# design.net
KiCad netlist of a schematic drawn in Altium Designer
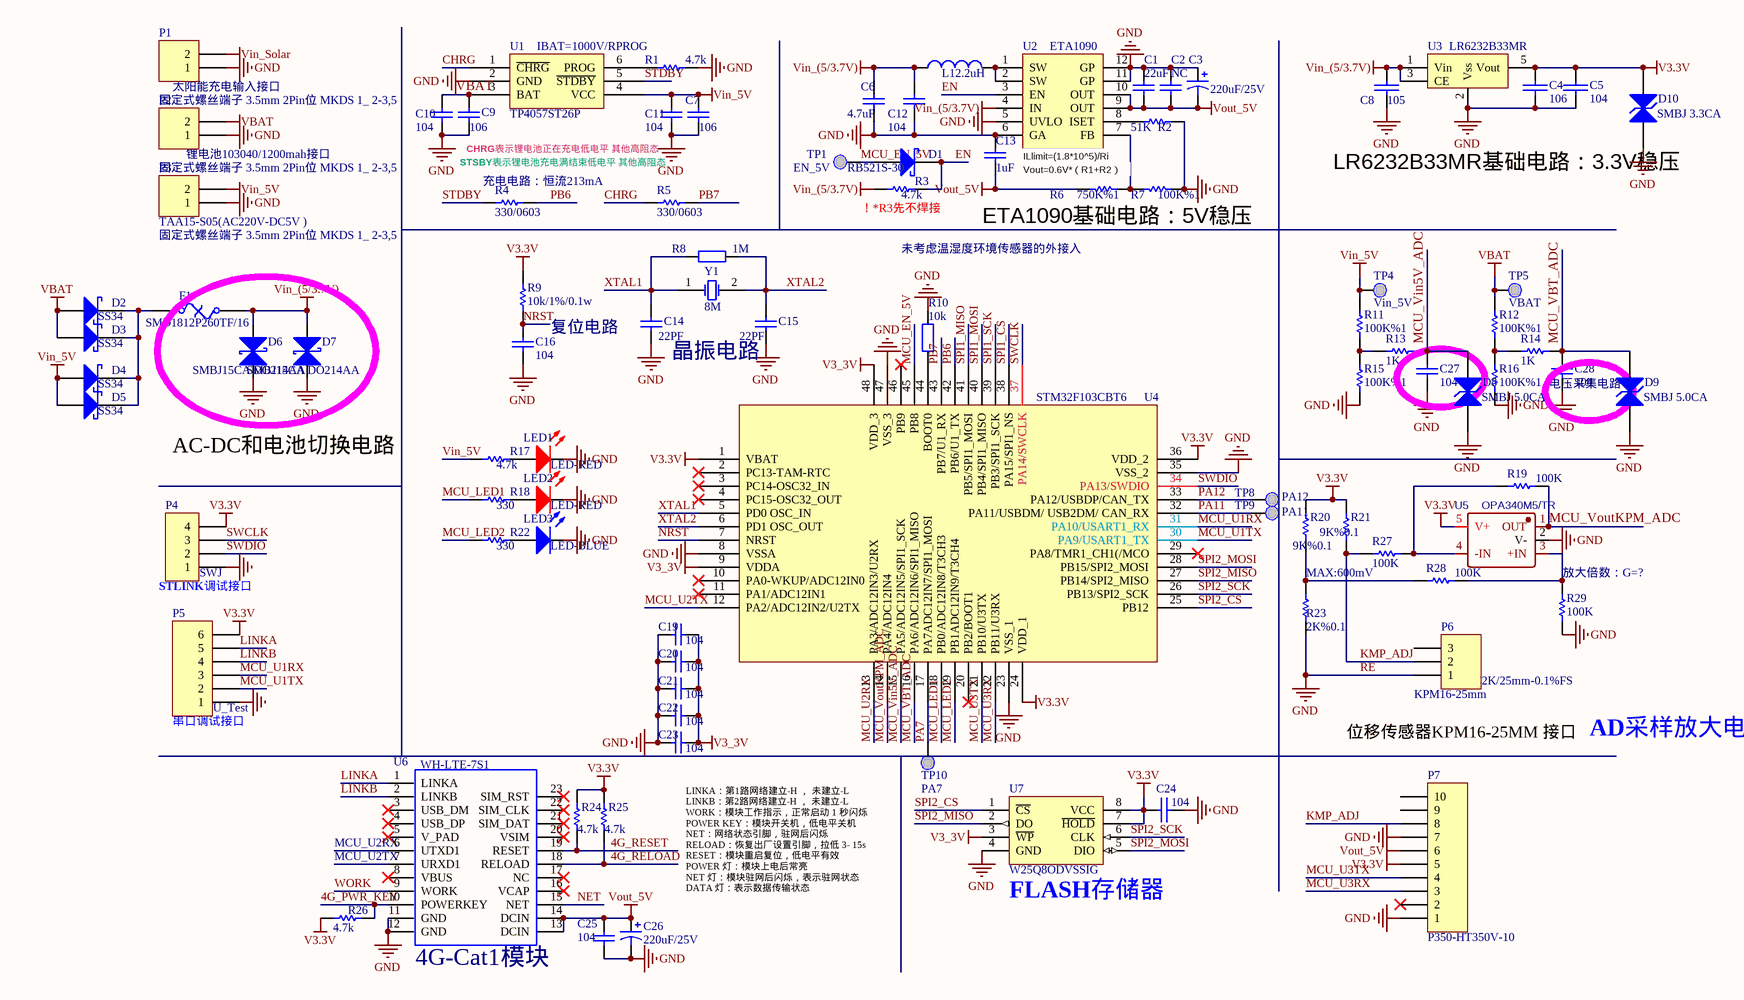
[diagram p0: 位移（应变）监测站.SchDoc]

(export (version "E")
  (design (tool "Eeschema 10.0.6"))
  (components
    (comp (ref "C1")
      (value "22uF")
      (footprint "C0805")
      (description "Capacitor")
      (fields (field (name "PUBLISHER") "Altium Limited"))
      (libsource (lib "Miscellaneous Devices") (part "Cap"))
    )
    (comp (ref "C2")
      (value "NC")
      (footprint "C0805")
      (description "Capacitor")
      (fields (field (name "Comment") "Cap") (field (name "PUBLISHER") "Altium Limited"))
      (libsource (lib "Miscellaneous Devices") (part "Cap"))
    )
    (comp (ref "C3")
      (value "220uF/25V")
      (footprint "C_6032")
      (description "Polarized Capacitor (Radial)")
      (fields (field (name "PUBLISHER") "Altium Limited"))
      (libsource (lib "Miscellaneous Devices") (part "Cap Pol1"))
    )
    (comp (ref "C4")
      (value "106")
      (footprint "C0603")
      (description "贴片电容")
      (libsource (lib "My_library") (part "CAP_1"))
    )
    (comp (ref "C5")
      (value "104")
      (footprint "C0603")
      (description "贴片电容")
      (libsource (lib "My_library") (part "CAP_1"))
    )
    (comp (ref "C6")
      (value "4.7uF")
      (footprint "C0603")
      (description "Capacitor")
      (fields (field (name "Comment") "Cap") (field (name "PUBLISHER") "Altium Limited"))
      (libsource (lib "Miscellaneous Devices") (part "Cap"))
    )
    (comp (ref "C7")
      (value "106")
      (footprint "C0603")
      (description "贴片电容")
      (fields (field (name "PUBLISHER") "Altium Limited"))
      (libsource (lib "*") (part "CAP"))
    )
    (comp (ref "C8")
      (value "105")
      (footprint "C0603")
      (description "贴片电容")
      (libsource (lib "My_library") (part "CAP_1"))
    )
    (comp (ref "C9")
      (value "106")
      (footprint "C0603")
      (description "贴片电容")
      (fields (field (name "PUBLISHER") "Altium Limited"))
      (libsource (lib "*") (part "CAP"))
    )
    (comp (ref "C10")
      (value "104")
      (footprint "C0603")
      (description "贴片电容")
      (fields (field (name "PUBLISHER") "Altium Limited"))
      (libsource (lib "*") (part "CAP"))
    )
    (comp (ref "C11")
      (value "104")
      (footprint "C0603")
      (description "贴片电容")
      (fields (field (name "PUBLISHER") "Altium Limited"))
      (libsource (lib "*") (part "CAP"))
    )
    (comp (ref "C12")
      (value "104")
      (footprint "C0603")
      (description "Capacitor")
      (fields (field (name "Comment") "Cap") (field (name "PUBLISHER") "Altium Limited"))
      (libsource (lib "Miscellaneous Devices") (part "Cap"))
    )
    (comp (ref "C13")
      (value "1uF")
      (footprint "C0603")
      (description "Capacitor")
      (fields (field (name "PUBLISHER") "Altium Limited"))
      (libsource (lib "Miscellaneous Devices") (part "Cap"))
    )
    (comp (ref "C14")
      (value "22PF")
      (footprint "C0603")
      (description "Capacitor")
      (fields (field (name "PUBLISHER") "Altium Limited"))
      (libsource (lib "Miscellaneous Devices") (part "Cap"))
    )
    (comp (ref "C15")
      (value "22PF")
      (footprint "C0603")
      (description "Capacitor")
      (fields (field (name "PUBLISHER") "Altium Limited"))
      (libsource (lib "Miscellaneous Devices") (part "Cap"))
    )
    (comp (ref "C16")
      (value "104")
      (footprint "C0603")
      (description "Capacitor")
      (fields (field (name "PUBLISHER") "Altium Limited"))
      (libsource (lib "*") (part "Cap"))
    )
    (comp (ref "C19")
      (value "104")
      (footprint "C0603")
      (description "Capacitor")
      (fields (field (name "PUBLISHER") "Altium Limited"))
      (libsource (lib "*") (part "CAP"))
    )
    (comp (ref "C20")
      (value "104")
      (footprint "C0603")
      (description "Capacitor")
      (fields (field (name "PUBLISHER") "Altium Limited"))
      (libsource (lib "*") (part "CAP"))
    )
    (comp (ref "C21")
      (value "104")
      (footprint "C0603")
      (description "Capacitor")
      (fields (field (name "PUBLISHER") "Altium Limited"))
      (libsource (lib "*") (part "CAP"))
    )
    (comp (ref "C22")
      (value "104")
      (footprint "C0603")
      (description "Capacitor")
      (fields (field (name "PUBLISHER") "Altium Limited"))
      (libsource (lib "*") (part "CAP"))
    )
    (comp (ref "C23")
      (value "104")
      (footprint "C0603")
      (description "Capacitor")
      (fields (field (name "PUBLISHER") "Altium Limited"))
      (libsource (lib "*") (part "CAP"))
    )
    (comp (ref "C24")
      (value "104")
      (footprint "C0603")
      (description "贴片电容")
      (libsource (lib "My_library") (part "CAP_1"))
    )
    (comp (ref "C25")
      (value "104")
      (footprint "C0603")
      (description "Capacitor")
      (fields (field (name "PUBLISHER") "Altium Limited"))
      (libsource (lib "*") (part "CAP"))
    )
    (comp (ref "C26")
      (value "220uF/25V")
      (footprint "C_6032")
      (description "Polarized Capacitor (Radial)")
      (fields (field (name "PUBLISHER") "Altium Limited"))
      (libsource (lib "Miscellaneous Devices") (part "Cap Pol1"))
    )
    (comp (ref "C27")
      (value "104")
      (footprint "C0603")
      (description "Capacitor")
      (fields (field (name "PUBLISHER") "Altium Limited"))
      (libsource (lib "*") (part "Cap"))
    )
    (comp (ref "C28")
      (value "104")
      (footprint "C0603")
      (description "Capacitor")
      (fields (field (name "PUBLISHER") "Altium Limited"))
      (libsource (lib "*") (part "Cap"))
    )
    (comp (ref "D1")
      (value "RB521S-30")
      (footprint "DO-214AB(SMC)")
      (description "肖特基二极管")
      (libsource (lib "My_library") (part "D Schottky"))
    )
    (comp (ref "D2")
      (value "SS34")
      (footprint "DO-214AB(SMC)")
      (description "肖特基二极管")
      (libsource (lib "My_library") (part "D Schottky"))
    )
    (comp (ref "D3")
      (value "SS34")
      (footprint "DO-214AB(SMC)")
      (description "肖特基二极管")
      (libsource (lib "My_library") (part "D Schottky"))
    )
    (comp (ref "D4")
      (value "SS34")
      (footprint "DO-214AB(SMC)")
      (description "肖特基二极管")
      (libsource (lib "My_library") (part "D Schottky"))
    )
    (comp (ref "D5")
      (value "SS34")
      (footprint "DO-214AB(SMC)")
      (description "肖特基二极管")
      (libsource (lib "My_library") (part "D Schottky"))
    )
    (comp (ref "D6")
      (value "SMBJ15CA DO214AA")
      (footprint "DO-214AA")
      (libsource (lib "自己的元器件库") (part "TVS"))
    )
    (comp (ref "D7")
      (value "SMBJ15CA DO214AA")
      (footprint "DO-214AA")
      (libsource (lib "自己的元器件库") (part "TVS"))
    )
    (comp (ref "D8")
      (value "SMBJ 5.0CA")
      (footprint "DO-214AA")
      (description "TVS")
      (libsource (lib "Miscellaneous Devices LC") (part "SMB/DO-214AA P6SMB6.8CA"))
    )
    (comp (ref "D9")
      (value "SMBJ 5.0CA")
      (footprint "DO-214AA")
      (description "TVS")
      (libsource (lib "Miscellaneous Devices LC") (part "SMB/DO-214AA P6SMB6.8CA"))
    )
    (comp (ref "D10")
      (value "SMBJ 3.3CA")
      (footprint "DO-214AA")
      (description "TVS")
      (libsource (lib "Miscellaneous Devices LC") (part "SMB/DO-214AA P6SMB6.8CA"))
    )
    (comp (ref "F1")
      (value "SMD1812P260TF/16")
      (footprint "1812")
      (description "Thermal Fuse")
      (fields (field (name "PUBLISHER") "Altium Limited"))
      (libsource (lib "Miscellaneous Devices") (part "Fuse Thermal"))
    )
    (comp (ref "L1")
      (value "2.2uH")
      (footprint "L_8X8")
      (description "Inductor")
      (fields (field (name "PUBLISHER") "Altium Limited"))
      (libsource (lib "Miscellaneous Devices") (part "Inductor"))
    )
    (comp (ref "LED1")
      (value "LED-RED")
      (footprint "0603_LED")
      (description "发光二极管")
      (libsource (lib "My_library") (part "LED-RED"))
    )
    (comp (ref "LED2")
      (value "LED-RED")
      (footprint "0603_LED")
      (description "发光二极管")
      (libsource (lib "My_library") (part "LED-RED"))
    )
    (comp (ref "LED3")
      (value "LED-BLUE")
      (footprint "0603_LED")
      (description "发光二极管")
      (libsource (lib "My_library") (part "LED-BLUE"))
    )
    (comp (ref "P1")
      (value "固定式螺丝端子 3.5mm 2Pin位 MKDS 1_ 2-3,5")
      (footprint "CONN-TH_MKDS1/2-3.5")
      (description "Header, 2-Pin")
      (fields (field (name "PUBLISHER") "Altium Limited"))
      (libsource (lib "Miscellaneous Connectors") (part "Header 2"))
    )
    (comp (ref "P2")
      (value "固定式螺丝端子 3.5mm 2Pin位 MKDS 1_ 2-3,5")
      (footprint "CONN-TH_MKDS1/2-3.5")
      (description "Header, 2-Pin")
      (fields (field (name "PUBLISHER") "Altium Limited"))
      (libsource (lib "Miscellaneous Connectors") (part "Header 2"))
    )
    (comp (ref "P3")
      (value "固定式螺丝端子 3.5mm 2Pin位 MKDS 1_ 2-3,5")
      (footprint "CONN-TH_MKDS1/2-3.5")
      (description "Header, 2-Pin")
      (fields (field (name "PUBLISHER") "Altium Limited"))
      (libsource (lib "Miscellaneous Connectors") (part "Header 2"))
    )
    (comp (ref "P4")
      (value "SWJ")
      (footprint "HDR1X4")
      (description "2.54接口，4pin")
      (libsource (lib "My_library") (part "header4"))
    )
    (comp (ref "P5")
      (value "U_Test")
      (footprint "HDR1X6")
      (description "Header, 6-Pin")
      (fields (field (name "PUBLISHER") "Altium Limited"))
      (libsource (lib "Miscellaneous Connectors") (part "Header 6"))
    )
    (comp (ref "P6")
      (value "~")
      (footprint "MHDR1X3")
      (description "航空插排（座）, 3-Pin")
      (fields (field (name "PUBLISHER") "Altium Limited"))
      (libsource (lib "Miscellaneous Connectors") (part "MHDR1X3"))
    )
    (comp (ref "P7")
      (value "P350-HT350V-10")
      (footprint "P350-HT350V-10")
      (description "Header, 10-Pin")
      (fields (field (name "PUBLISHER") "Altium Limited"))
      (libsource (lib "Miscellaneous Connectors") (part "Header 10"))
    )
    (comp (ref "R1")
      (value "4.7k")
      (footprint "R0603")
      (description "贴片电阻")
      (libsource (lib "My_library") (part "RES1"))
    )
    (comp (ref "R2")
      (value "51K")
      (footprint "R0603")
      (description "Resistor")
      (fields (field (name "PUBLISHER") "Altium Limited"))
      (libsource (lib "Miscellaneous Devices") (part "Res1"))
    )
    (comp (ref "R3")
      (value "4.7k")
      (footprint "R0603")
      (description "贴片电阻")
      (libsource (lib "My_library") (part "RES1"))
    )
    (comp (ref "R4")
      (value "330/0603")
      (footprint "R0603")
      (description "Resistor")
      (fields (field (name "PUBLISHER") "Altium Limited"))
      (libsource (lib "*") (part "Res1"))
    )
    (comp (ref "R5")
      (value "330/0603")
      (footprint "R0603")
      (description "Resistor")
      (fields (field (name "PUBLISHER") "Altium Limited"))
      (libsource (lib "*") (part "Res1"))
    )
    (comp (ref "R6")
      (value "750K%1")
      (footprint "R0603")
      (description "Resistor")
      (fields (field (name "PUBLISHER") "Altium Limited"))
      (libsource (lib "Miscellaneous Devices") (part "Res1"))
    )
    (comp (ref "R7")
      (value "100K%1")
      (footprint "R0603")
      (description "Resistor")
      (fields (field (name "PUBLISHER") "Altium Limited"))
      (libsource (lib "Miscellaneous Devices") (part "Res1"))
    )
    (comp (ref "R8")
      (value "1M")
      (footprint "R0603")
      (description "Resistor")
      (fields (field (name "PUBLISHER") "Altium Limited"))
      (libsource (lib "Miscellaneous Devices") (part "Res2"))
    )
    (comp (ref "R9")
      (value "10k/1%/0.1w")
      (footprint "R0603")
      (description "Resistor")
      (fields (field (name "PUBLISHER") "Altium Limited"))
      (libsource (lib "*") (part "res1"))
    )
    (comp (ref "R10")
      (value "10k")
      (footprint "R0603")
      (description "Resistor")
      (fields (field (name "PUBLISHER") "Altium Limited"))
      (libsource (lib "") (part "Res2_1"))
    )
    (comp (ref "R11")
      (value "100K%1")
      (footprint "R0603")
      (description "贴片电阻")
      (libsource (lib "My_library") (part "RES1"))
    )
    (comp (ref "R12")
      (value "100K%1")
      (footprint "R0603")
      (description "贴片电阻")
      (libsource (lib "My_library") (part "RES1"))
    )
    (comp (ref "R13")
      (value "1K")
      (footprint "R0603")
      (description "贴片电阻")
      (libsource (lib "My_library") (part "RES1"))
    )
    (comp (ref "R14")
      (value "1K")
      (footprint "R0603")
      (description "贴片电阻")
      (libsource (lib "My_library") (part "RES1"))
    )
    (comp (ref "R15")
      (value "100K%1")
      (footprint "R0603")
      (description "贴片电阻")
      (libsource (lib "My_library") (part "RES1"))
    )
    (comp (ref "R16")
      (value "100K%1")
      (footprint "R0603")
      (description "贴片电阻")
      (libsource (lib "My_library") (part "RES1"))
    )
    (comp (ref "R17")
      (value "4.7k")
      (footprint "R0603")
      (description "贴片电阻")
      (libsource (lib "My_library") (part "RES1"))
    )
    (comp (ref "R18")
      (value "330")
      (footprint "R0603")
      (description "贴片电阻")
      (libsource (lib "My_library") (part "RES1"))
    )
    (comp (ref "R19")
      (value "100K")
      (footprint "R0603")
      (description "贴片电阻")
      (libsource (lib "My_library") (part "RES1"))
    )
    (comp (ref "R20")
      (value "9K%0.1")
      (footprint "R0603")
      (description "贴片电阻")
      (libsource (lib "My_library") (part "RES1"))
    )
    (comp (ref "R21")
      (value "9K%0.1")
      (footprint "R0603")
      (description "贴片电阻")
      (libsource (lib "My_library") (part "RES1"))
    )
    (comp (ref "R22")
      (value "330")
      (footprint "R0603")
      (description "贴片电阻")
      (libsource (lib "My_library") (part "RES1"))
    )
    (comp (ref "R23")
      (value "2K%0.1")
      (footprint "R0603")
      (description "贴片电阻")
      (libsource (lib "My_library") (part "RES1"))
    )
    (comp (ref "R24")
      (value "4.7k")
      (footprint "R0603")
      (description "Resistor")
      (fields (field (name "PUBLISHER") "Altium Limited"))
      (libsource (lib "*") (part "Res1"))
    )
    (comp (ref "R25")
      (value "4.7k")
      (footprint "R0603")
      (description "Resistor")
      (fields (field (name "PUBLISHER") "Altium Limited"))
      (libsource (lib "*") (part "Res1"))
    )
    (comp (ref "R26")
      (value "4.7k")
      (footprint "R0603")
      (description "Resistor")
      (fields (field (name "PUBLISHER") "Altium Limited"))
      (libsource (lib "*") (part "Res1"))
    )
    (comp (ref "R27")
      (value "100K")
      (footprint "R0603")
      (description "贴片电阻")
      (libsource (lib "My_library") (part "RES1"))
    )
    (comp (ref "R28")
      (value "100K")
      (footprint "R0603")
      (description "贴片电阻")
      (libsource (lib "My_library") (part "RES1"))
    )
    (comp (ref "R29")
      (value "100K")
      (footprint "R0603")
      (description "贴片电阻")
      (libsource (lib "My_library") (part "RES1"))
    )
    (comp (ref "TP1")
      (value "EN_5V")
      (footprint "TESTPOINT_1*1mm")
      (libsource (lib "BASIC_DEVICES") (part "TEST_Piont"))
    )
    (comp (ref "TP4")
      (value "Vin_5V")
      (footprint "TESTPOINT_1*1mm")
      (libsource (lib "BASIC_DEVICES") (part "TEST_Piont"))
    )
    (comp (ref "TP5")
      (value "VBAT")
      (footprint "TESTPOINT_1*1mm")
      (libsource (lib "BASIC_DEVICES") (part "TEST_Piont"))
    )
    (comp (ref "TP8")
      (value "PA12")
      (footprint "TESTPOINT_1*1mm")
      (libsource (lib "BASIC_DEVICES") (part "TEST_Piont"))
    )
    (comp (ref "TP9")
      (value "PA11")
      (footprint "TESTPOINT_1*1mm")
      (libsource (lib "BASIC_DEVICES") (part "TEST_Piont"))
    )
    (comp (ref "TP10")
      (value "PA7")
      (footprint "TESTPOINT_1*1mm")
      (libsource (lib "BASIC_DEVICES") (part "TEST_Piont"))
    )
    (comp (ref "U1")
      (value "TP4057ST26P")
      (footprint "监测站_PCBLIB:SOT23-6L")
      (description "充电芯片")
      (libsource (lib "TP4057ST26P") (part "Component_1"))
    )
    (comp (ref "U2")
      (value "ETA1090")
      (footprint "DFN3x3_12")
      (description "5V稳压电路")
      (fields (field (name "PUBLISHER") "Altium Limited"))
      (libsource (lib "PCB_Project1") (part "Header 6X2H"))
    )
    (comp (ref "U3")
      (value "LR6232B33MR")
      (footprint "SOT23-5_LR6232B33M")
      (description "3.3V稳压芯片")
      (libsource (lib "My_library") (part "XC6221-xxxMR"))
    )
    (comp (ref "U4")
      (value "STM32F103CBT6")
      (footprint "STM32F103CBT6")
      (description "MCU主控")
      (libsource (lib "STM32F103CBT6") (part "Component_1"))
    )
    (comp (ref "U5")
      (value "OPA340M5/TR")
      (footprint "SOT-23-5_L3.0-W1.7-P0.95-LS2.8-BL")
      (fields (field (name "BOM_SUPPLIER PART") "C565341") (field (name "CONTRIBUTOR") "LCSC"))
      (libsource (lib "altium-import") (part "root_0_mirrored_OPA340M5/TR_"))
    )
    (comp (ref "U6")
      (value "WH-LTE-7S1")
      (footprint "WH-LTE-7S1")
      (description "4G-Cat1模块")
      (libsource (lib "WH-LTE-7S1") (part "WH-LTE-7S1"))
    )
    (comp (ref "U7")
      (value "W25Q8ODVSSIG")
      (footprint "SOIC-8 208-mil")
      (description "华邦 NOR Flash存储器/SOIC-8 208-mil")
      (libsource (lib "My_library") (part "W25-Series"))
    )
    (comp (ref "Y1")
      (value "8M")
      (footprint "XT_SMD_5032_2P")
      (description "Crystal Oscillator")
      (fields (field (name "PUBLISHER") "Altium Limited"))
      (libsource (lib "Miscellaneous Devices") (part "XTAL"))
    )
  )
  (nets
    (net (code "1") (name "/4G_PWR_KEY") (class "Default")
      (node (ref "R26") (pin "1") (pinfunction "1_1") (pintype "passive"))
      (node (ref "U6") (pin "10") (pinfunction "POWERKEY_10") (pintype "passive"))
    )
    (net (code "2") (name "/4G_RELOAD") (class "Default")
      (node (ref "R25") (pin "2") (pinfunction "2_2") (pintype "passive"))
      (node (ref "U6") (pin "18") (pinfunction "RELOAD_18") (pintype "passive"))
    )
    (net (code "3") (name "/4G_RESET") (class "Default")
      (node (ref "R24") (pin "2") (pinfunction "2_2") (pintype "passive"))
      (node (ref "U6") (pin "19") (pinfunction "RESET_19") (pintype "passive"))
    )
    (net (code "4") (name "/CHRG") (class "Default")
      (node (ref "R5") (pin "1") (pinfunction "1_1") (pintype "passive"))
      (node (ref "U1") (pin "1") (pinfunction "~{CHRG}_1") (pintype "passive"))
    )
    (net (code "5") (name "/EN") (class "Default")
      (node (ref "D1") (pin "2") (pinfunction "K_2") (pintype "passive"))
      (node (ref "R3") (pin "2") (pinfunction "2_2") (pintype "passive"))
      (node (ref "U2") (pin "3") (pinfunction "EN_3") (pintype "passive"))
    )
    (net (code "6") (name "/KMP_ADJ") (class "Default")
      (node (ref "P6") (pin "2") (pinfunction "2_2") (pintype "passive"))
      (node (ref "P7") (pin "8") (pinfunction "8_8") (pintype "passive"))
      (node (ref "R21") (pin "2") (pinfunction "2_2") (pintype "passive"))
      (node (ref "R27") (pin "2") (pinfunction "2_2") (pintype "passive"))
    )
    (net (code "7") (name "/LINKA") (class "Default")
      (node (ref "P5") (pin "5") (pinfunction "5_5") (pintype "passive"))
      (node (ref "U6") (pin "1") (pinfunction "LINKA_1") (pintype "passive"))
    )
    (net (code "8") (name "/LINKB") (class "Default")
      (node (ref "P5") (pin "4") (pinfunction "4_4") (pintype "passive"))
      (node (ref "U6") (pin "2") (pinfunction "LINKB_2") (pintype "passive"))
    )
    (net (code "9") (name "/MCU_EN_5V") (class "Default")
      (node (ref "D1") (pin "1") (pinfunction "A_1") (pintype "passive"))
      (node (ref "TP1") (pin "1") (pinfunction "T_1") (pintype "passive"))
      (node (ref "U4") (pin "45") (pinfunction "PB8_45") (pintype "passive"))
    )
    (net (code "10") (name "/MCU_LED1") (class "Default")
      (node (ref "R18") (pin "1") (pinfunction "1_1") (pintype "passive"))
      (node (ref "U4") (pin "18") (pinfunction "PB0/ADC12IN8/T3CH3_18") (pintype "passive"))
    )
    (net (code "11") (name "/MCU_LED2") (class "Default")
      (node (ref "R22") (pin "1") (pinfunction "1_1") (pintype "passive"))
      (node (ref "U4") (pin "19") (pinfunction "PB1ADC12IN9/T3CH4_19") (pintype "passive"))
    )
    (net (code "12") (name "/MCU_U1RX") (class "Default")
      (node (ref "P5") (pin "3") (pinfunction "3_3") (pintype "passive"))
      (node (ref "U4") (pin "31") (pinfunction "PA10/USART1_RX_31") (pintype "passive"))
    )
    (net (code "13") (name "/MCU_U1TX") (class "Default")
      (node (ref "P5") (pin "2") (pinfunction "2_2") (pintype "passive"))
      (node (ref "U4") (pin "30") (pinfunction "PA9/USART1_TX_30") (pintype "passive"))
    )
    (net (code "14") (name "/MCU_U2RX") (class "Default")
      (node (ref "U4") (pin "13") (pinfunction "PA3/ADC12IN3/U2RX_13") (pintype "passive"))
      (node (ref "U6") (pin "6") (pinfunction "UTXD1_6") (pintype "passive"))
    )
    (net (code "15") (name "/MCU_U2TX") (class "Default")
      (node (ref "U4") (pin "12") (pinfunction "PA2/ADC12IN2/U2TX_12") (pintype "passive"))
      (node (ref "U6") (pin "7") (pinfunction "URXD1_7") (pintype "passive"))
    )
    (net (code "16") (name "/MCU_U3RX") (class "Default")
      (node (ref "P7") (pin "3") (pinfunction "3_3") (pintype "passive"))
      (node (ref "U4") (pin "22") (pinfunction "PB11/U3RX_22") (pintype "passive"))
    )
    (net (code "17") (name "/MCU_U3TX") (class "Default")
      (node (ref "P7") (pin "4") (pinfunction "4_4") (pintype "passive"))
      (node (ref "U4") (pin "21") (pinfunction "PB10/U3TX_21") (pintype "passive"))
    )
    (net (code "18") (name "/MCU_VBT_ADC") (class "Default")
      (node (ref "C28") (pin "1") (pinfunction "1_1") (pintype "passive"))
      (node (ref "D9") (pin "2") (pinfunction "K_2") (pintype "passive"))
      (node (ref "R14") (pin "1") (pinfunction "1_1") (pintype "passive"))
      (node (ref "U4") (pin "16") (pinfunction "PA6/ADC12IN6/SPI1_MISO_16") (pintype "passive"))
    )
    (net (code "19") (name "/MCU_Vin5V_ADC") (class "Default")
      (node (ref "C27") (pin "1") (pinfunction "1_1") (pintype "passive"))
      (node (ref "D8") (pin "2") (pinfunction "K_2") (pintype "passive"))
      (node (ref "R13") (pin "2") (pinfunction "2_2") (pintype "passive"))
      (node (ref "U4") (pin "15") (pinfunction "PA5/ADC12IN5/SPI1_SCK_15") (pintype "passive"))
    )
    (net (code "20") (name "/MCU_VoutKPM_ADC") (class "Default")
      (node (ref "R19") (pin "1") (pinfunction "1_1") (pintype "passive"))
      (node (ref "U4") (pin "14") (pinfunction "PA4/ADC12IN4_14") (pintype "passive"))
      (node (ref "U5") (pin "1") (pinfunction "OUT_1") (pintype "passive"))
    )
    (net (code "21") (name "/NET") (class "Default")
      (node (ref "U6") (pin "15") (pinfunction "NET_15") (pintype "passive"))
    )
    (net (code "22") (name "/NRST") (class "Default")
      (node (ref "C16") (pin "1") (pinfunction "1_1") (pintype "passive"))
      (node (ref "R9") (pin "1") (pinfunction "1_1") (pintype "passive"))
      (node (ref "U4") (pin "7") (pinfunction "NRST_7") (pintype "passive"))
    )
    (net (code "23") (name "/PA7") (class "Default")
      (node (ref "TP10") (pin "1") (pinfunction "T_1") (pintype "passive"))
      (node (ref "U4") (pin "17") (pinfunction "PA7ADC12IN7/SPI1_MOSI_17") (pintype "passive"))
    )
    (net (code "24") (name "/PA11") (class "Default")
      (node (ref "TP9") (pin "1") (pinfunction "T_1") (pintype "passive"))
      (node (ref "U4") (pin "32") (pinfunction "PA11/USBDM/_USB2DM/_CAN_RX_32") (pintype "passive"))
    )
    (net (code "25") (name "/PA12") (class "Default")
      (node (ref "TP8") (pin "1") (pinfunction "T_1") (pintype "passive"))
      (node (ref "U4") (pin "33") (pinfunction "PA12/USBDP/CAN_TX_33") (pintype "passive"))
    )
    (net (code "26") (name "/PB6") (class "Default")
      (node (ref "R4") (pin "2") (pinfunction "2_2") (pintype "passive"))
      (node (ref "U4") (pin "42") (pinfunction "PB6/U1_TX_42") (pintype "passive"))
    )
    (net (code "27") (name "/PB7") (class "Default")
      (node (ref "R5") (pin "2") (pinfunction "2_2") (pintype "passive"))
      (node (ref "U4") (pin "43") (pinfunction "PB7/U1_RX_43") (pintype "passive"))
    )
    (net (code "28") (name "/SPI1_CS") (class "Default")
      (node (ref "U4") (pin "38") (pinfunction "PA15/SPI1_NS_38") (pintype "passive"))
    )
    (net (code "29") (name "/SPI1_MISO") (class "Default")
      (node (ref "U4") (pin "41") (pinfunction "PB5/SPI1_MOSI_41") (pintype "passive"))
    )
    (net (code "30") (name "/SPI1_MOSI") (class "Default")
      (node (ref "U4") (pin "40") (pinfunction "PB4/SPI1_MISO_40") (pintype "passive"))
    )
    (net (code "31") (name "/SPI1_SCK") (class "Default")
      (node (ref "U4") (pin "39") (pinfunction "PB3/SPI1_SCK_39") (pintype "passive"))
    )
    (net (code "32") (name "/SPI2_CS") (class "Default")
      (node (ref "U4") (pin "25") (pinfunction "PB12_25") (pintype "passive"))
      (node (ref "U7") (pin "1") (pinfunction "~{CS}_1") (pintype "passive"))
    )
    (net (code "33") (name "/SPI2_MISO") (class "Default")
      (node (ref "U4") (pin "27") (pinfunction "PB14/SPI2_MISO_27") (pintype "passive"))
      (node (ref "U7") (pin "2") (pinfunction "DO_2") (pintype "output"))
    )
    (net (code "34") (name "/SPI2_MOSI") (class "Default")
      (node (ref "U4") (pin "28") (pinfunction "PB15/SPI2_MOSI_28") (pintype "passive"))
      (node (ref "U7") (pin "5") (pinfunction "DIO_5") (pintype "bidirectional"))
    )
    (net (code "35") (name "/SPI2_SCK") (class "Default")
      (node (ref "U4") (pin "26") (pinfunction "PB13/SPI2_SCK_26") (pintype "passive"))
      (node (ref "U7") (pin "6") (pinfunction "CLK_6") (pintype "input"))
    )
    (net (code "36") (name "/STDBY") (class "Default")
      (node (ref "R4") (pin "1") (pinfunction "1_1") (pintype "passive"))
      (node (ref "U1") (pin "5") (pinfunction "~{STDBY}_5") (pintype "passive"))
    )
    (net (code "37") (name "/SWCLK") (class "Default")
      (node (ref "P4") (pin "3") (pinfunction "3_3") (pintype "passive"))
      (node (ref "U4") (pin "37") (pinfunction "PA14/SWCLK_37") (pintype "passive"))
    )
    (net (code "38") (name "/SWDIO") (class "Default")
      (node (ref "P4") (pin "2") (pinfunction "2_2") (pintype "passive"))
      (node (ref "U4") (pin "34") (pinfunction "PA13/SWDIO_34") (pintype "passive"))
    )
    (net (code "39") (name "/WORK") (class "Default")
      (node (ref "U6") (pin "9") (pinfunction "WORK_9") (pintype "passive"))
    )
    (net (code "40") (name "/XTAL1") (class "Default")
      (node (ref "C14") (pin "1") (pinfunction "1_1") (pintype "passive"))
      (node (ref "R8") (pin "2") (pinfunction "2_2") (pintype "passive"))
      (node (ref "U4") (pin "5") (pinfunction "PD0_OSC_IN_5") (pintype "passive"))
      (node (ref "Y1") (pin "1") (pinfunction "OSC1_1") (pintype "passive"))
    )
    (net (code "41") (name "/XTAL2") (class "Default")
      (node (ref "C15") (pin "1") (pinfunction "1_1") (pintype "passive"))
      (node (ref "R8") (pin "1") (pinfunction "1_1") (pintype "passive"))
      (node (ref "U4") (pin "6") (pinfunction "PD1_OSC_OUT_6") (pintype "passive"))
      (node (ref "Y1") (pin "2") (pinfunction "OSC2_2") (pintype "passive"))
    )
    (net (code "42") (name "GND") (class "Default")
      (node (ref "C1") (pin "2") (pinfunction "2_2") (pintype "passive"))
      (node (ref "C10") (pin "1") (pinfunction "1_1") (pintype "passive"))
      (node (ref "C11") (pin "1") (pinfunction "1_1") (pintype "passive"))
      (node (ref "C12") (pin "1") (pinfunction "1_1") (pintype "passive"))
      (node (ref "C13") (pin "2") (pinfunction "2_2") (pintype "passive"))
      (node (ref "C14") (pin "2") (pinfunction "2_2") (pintype "passive"))
      (node (ref "C15") (pin "2") (pinfunction "2_2") (pintype "passive"))
      (node (ref "C16") (pin "2") (pinfunction "2_2") (pintype "passive"))
      (node (ref "C19") (pin "2") (pinfunction "2_2") (pintype "passive"))
      (node (ref "C2") (pin "2") (pinfunction "2_2") (pintype "passive"))
      (node (ref "C20") (pin "2") (pinfunction "2_2") (pintype "passive"))
      (node (ref "C21") (pin "2") (pinfunction "2_2") (pintype "passive"))
      (node (ref "C22") (pin "2") (pinfunction "2_2") (pintype "passive"))
      (node (ref "C23") (pin "2") (pinfunction "2_2") (pintype "passive"))
      (node (ref "C24") (pin "2") (pinfunction "2_2") (pintype "passive"))
      (node (ref "C25") (pin "1") (pinfunction "1_1") (pintype "passive"))
      (node (ref "C26") (pin "2") (pinfunction "2_2") (pintype "passive"))
      (node (ref "C27") (pin "2") (pinfunction "2_2") (pintype "passive"))
      (node (ref "C28") (pin "2") (pinfunction "2_2") (pintype "passive"))
      (node (ref "C3") (pin "1") (pinfunction "1_1") (pintype "passive"))
      (node (ref "C4") (pin "2") (pinfunction "2_2") (pintype "passive"))
      (node (ref "C5") (pin "2") (pinfunction "2_2") (pintype "passive"))
      (node (ref "C6") (pin "1") (pinfunction "1_1") (pintype "passive"))
      (node (ref "C7") (pin "2") (pinfunction "2_2") (pintype "passive"))
      (node (ref "C8") (pin "2") (pinfunction "2_2") (pintype "passive"))
      (node (ref "C9") (pin "2") (pinfunction "2_2") (pintype "passive"))
      (node (ref "D10") (pin "1") (pinfunction "A_1") (pintype "passive"))
      (node (ref "D6") (pin "1") (pinfunction "A_1") (pintype "passive"))
      (node (ref "D7") (pin "1") (pinfunction "A_1") (pintype "passive"))
      (node (ref "D8") (pin "1") (pinfunction "A_1") (pintype "passive"))
      (node (ref "D9") (pin "1") (pinfunction "A_1") (pintype "passive"))
      (node (ref "LED1") (pin "2") (pinfunction "K_2") (pintype "passive"))
      (node (ref "LED2") (pin "2") (pinfunction "K_2") (pintype "passive"))
      (node (ref "LED3") (pin "2") (pinfunction "K_2") (pintype "passive"))
      (node (ref "P1") (pin "1") (pinfunction "1_1") (pintype "passive"))
      (node (ref "P2") (pin "1") (pinfunction "1_1") (pintype "passive"))
      (node (ref "P3") (pin "1") (pinfunction "1_1") (pintype "passive"))
      (node (ref "P4") (pin "1") (pinfunction "1_1") (pintype "passive"))
      (node (ref "P5") (pin "1") (pinfunction "1_1") (pintype "passive"))
      (node (ref "P6") (pin "1") (pinfunction "1_1") (pintype "passive"))
      (node (ref "P7") (pin "1") (pinfunction "1_1") (pintype "passive"))
      (node (ref "P7") (pin "7") (pinfunction "7_7") (pintype "passive"))
      (node (ref "R1") (pin "1") (pinfunction "1_1") (pintype "passive"))
      (node (ref "R10") (pin "1") (pinfunction "1_1") (pintype "passive"))
      (node (ref "R15") (pin "2") (pinfunction "2_2") (pintype "passive"))
      (node (ref "R16") (pin "1") (pinfunction "1_1") (pintype "passive"))
      (node (ref "R2") (pin "1") (pinfunction "1_1") (pintype "passive"))
      (node (ref "R23") (pin "1") (pinfunction "1_1") (pintype "passive"))
      (node (ref "R29") (pin "2") (pinfunction "2_2") (pintype "passive"))
      (node (ref "R7") (pin "1") (pinfunction "1_1") (pintype "passive"))
      (node (ref "U1") (pin "2") (pinfunction "GND_2") (pintype "passive"))
      (node (ref "U2") (pin "11") (pinfunction "GP_11") (pintype "passive"))
      (node (ref "U2") (pin "12") (pinfunction "GP_12") (pintype "passive"))
      (node (ref "U2") (pin "5") (pinfunction "UVLO_5") (pintype "passive"))
      (node (ref "U2") (pin "6") (pinfunction "GA_6") (pintype "passive"))
      (node (ref "U3") (pin "2") (pinfunction "Vss_2") (pintype "passive"))
      (node (ref "U4") (pin "23") (pinfunction "VSS_1_23") (pintype "passive"))
      (node (ref "U4") (pin "35") (pinfunction "VSS_2_35") (pintype "passive"))
      (node (ref "U4") (pin "47") (pinfunction "VSS_3_47") (pintype "passive"))
      (node (ref "U4") (pin "8") (pinfunction "VSSA_8") (pintype "passive"))
      (node (ref "U5") (pin "2") (pinfunction "V-_2") (pintype "passive"))
      (node (ref "U6") (pin "11") (pinfunction "GND_11") (pintype "passive"))
      (node (ref "U6") (pin "12") (pinfunction "GND_12") (pintype "passive"))
      (node (ref "U7") (pin "4") (pinfunction "GND_4") (pintype "power_in"))
    )
    (net (code "43") (name "Net-(D2-K)") (class "Default")
      (node (ref "D2") (pin "2") (pinfunction "K_2") (pintype "passive"))
      (node (ref "D3") (pin "2") (pinfunction "K_2") (pintype "passive"))
      (node (ref "D4") (pin "2") (pinfunction "K_2") (pintype "passive"))
      (node (ref "D5") (pin "2") (pinfunction "K_2") (pintype "passive"))
      (node (ref "F1") (pin "1") (pinfunction "1_1") (pintype "passive"))
    )
    (net (code "44") (name "Net-(L1-Pad1)") (class "Default")
      (node (ref "L1") (pin "1") (pinfunction "1_1") (pintype "passive"))
      (node (ref "U2") (pin "1") (pinfunction "SW_1") (pintype "passive"))
      (node (ref "U2") (pin "2") (pinfunction "SW_2") (pintype "passive"))
    )
    (net (code "45") (name "Net-(LED1-A)") (class "Default")
      (node (ref "LED1") (pin "1") (pinfunction "A_1") (pintype "passive"))
      (node (ref "R17") (pin "2") (pinfunction "2_2") (pintype "passive"))
    )
    (net (code "46") (name "Net-(LED2-A)") (class "Default")
      (node (ref "LED2") (pin "1") (pinfunction "A_1") (pintype "passive"))
      (node (ref "R18") (pin "2") (pinfunction "2_2") (pintype "passive"))
    )
    (net (code "47") (name "Net-(LED3-A)") (class "Default")
      (node (ref "LED3") (pin "1") (pinfunction "A_1") (pintype "passive"))
      (node (ref "R22") (pin "2") (pinfunction "2_2") (pintype "passive"))
    )
    (net (code "48") (name "Net-(R11-Pad2)") (class "Default")
      (node (ref "R11") (pin "2") (pinfunction "2_2") (pintype "passive"))
      (node (ref "R13") (pin "1") (pinfunction "1_1") (pintype "passive"))
      (node (ref "R15") (pin "1") (pinfunction "1_1") (pintype "passive"))
    )
    (net (code "49") (name "Net-(R12-Pad1)") (class "Default")
      (node (ref "R12") (pin "1") (pinfunction "1_1") (pintype "passive"))
      (node (ref "R14") (pin "2") (pinfunction "2_2") (pintype "passive"))
      (node (ref "R16") (pin "2") (pinfunction "2_2") (pintype "passive"))
    )
    (net (code "50") (name "Net-(R20-Pad1)") (class "Default")
      (node (ref "R20") (pin "1") (pinfunction "1_1") (pintype "passive"))
      (node (ref "R23") (pin "2") (pinfunction "2_2") (pintype "passive"))
      (node (ref "R28") (pin "2") (pinfunction "2_2") (pintype "passive"))
    )
    (net (code "51") (name "Net-(U1-PROG)") (class "Default")
      (node (ref "R1") (pin "2") (pinfunction "2_2") (pintype "passive"))
      (node (ref "U1") (pin "6") (pinfunction "PROG_6") (pintype "passive"))
    )
    (net (code "52") (name "Net-(U2-FB)") (class "Default")
      (node (ref "R6") (pin "1") (pinfunction "1_1") (pintype "passive"))
      (node (ref "R7") (pin "2") (pinfunction "2_2") (pintype "passive"))
      (node (ref "U2") (pin "7") (pinfunction "FB_7") (pintype "passive"))
    )
    (net (code "53") (name "Net-(U2-ISET)") (class "Default")
      (node (ref "R2") (pin "2") (pinfunction "2_2") (pintype "passive"))
      (node (ref "U2") (pin "8") (pinfunction "ISET_8") (pintype "passive"))
    )
    (net (code "54") (name "Net-(U4-BOOT0)") (class "Default")
      (node (ref "R10") (pin "2") (pinfunction "2_2") (pintype "passive"))
      (node (ref "U4") (pin "44") (pinfunction "BOOT0_44") (pintype "passive"))
    )
    (net (code "55") (name "Net-(U5-+IN)") (class "Default")
      (node (ref "R28") (pin "1") (pinfunction "1_1") (pintype "passive"))
      (node (ref "R29") (pin "1") (pinfunction "1_1") (pintype "passive"))
      (node (ref "U5") (pin "3") (pinfunction "+IN_3") (pintype "passive"))
    )
    (net (code "56") (name "Net-(U5--IN)") (class "Default")
      (node (ref "R19") (pin "2") (pinfunction "2_2") (pintype "passive"))
      (node (ref "R27") (pin "1") (pinfunction "1_1") (pintype "passive"))
      (node (ref "U5") (pin "4") (pinfunction "-IN_4") (pintype "passive"))
    )
    (net (code "57") (name "V3.3V") (class "Default")
      (node (ref "C24") (pin "1") (pinfunction "1_1") (pintype "passive"))
      (node (ref "C4") (pin "1") (pinfunction "1_1") (pintype "passive"))
      (node (ref "C5") (pin "1") (pinfunction "1_1") (pintype "passive"))
      (node (ref "D10") (pin "2") (pinfunction "K_2") (pintype "passive"))
      (node (ref "P4") (pin "4") (pinfunction "4_4") (pintype "passive"))
      (node (ref "P5") (pin "6") (pinfunction "6_6") (pintype "passive"))
      (node (ref "P7") (pin "5") (pinfunction "5_5") (pintype "passive"))
      (node (ref "R20") (pin "2") (pinfunction "2_2") (pintype "passive"))
      (node (ref "R21") (pin "1") (pinfunction "1_1") (pintype "passive"))
      (node (ref "R24") (pin "1") (pinfunction "1_1") (pintype "passive"))
      (node (ref "R25") (pin "1") (pinfunction "1_1") (pintype "passive"))
      (node (ref "R26") (pin "2") (pinfunction "2_2") (pintype "passive"))
      (node (ref "R9") (pin "2") (pinfunction "2_2") (pintype "passive"))
      (node (ref "U3") (pin "5") (pinfunction "Vout_5") (pintype "passive"))
      (node (ref "U4") (pin "1") (pinfunction "VBAT_1") (pintype "passive"))
      (node (ref "U4") (pin "24") (pinfunction "VDD_1_24") (pintype "passive"))
      (node (ref "U4") (pin "36") (pinfunction "VDD_2_36") (pintype "passive"))
      (node (ref "U5") (pin "5") (pinfunction "V+_5") (pintype "passive"))
      (node (ref "U7") (pin "7") (pinfunction "~{HOLD}_7") (pintype "passive"))
      (node (ref "U7") (pin "8") (pinfunction "VCC_8") (pintype "power_in"))
    )
    (net (code "58") (name "V3_3V") (class "Default")
      (node (ref "C19") (pin "1") (pinfunction "1_1") (pintype "passive"))
      (node (ref "C20") (pin "1") (pinfunction "1_1") (pintype "passive"))
      (node (ref "C21") (pin "1") (pinfunction "1_1") (pintype "passive"))
      (node (ref "C22") (pin "1") (pinfunction "1_1") (pintype "passive"))
      (node (ref "C23") (pin "1") (pinfunction "1_1") (pintype "passive"))
      (node (ref "U4") (pin "48") (pinfunction "VDD_3_48") (pintype "passive"))
      (node (ref "U4") (pin "9") (pinfunction "VDDA_9") (pintype "passive"))
      (node (ref "U7") (pin "3") (pinfunction "~{WP}_3") (pintype "passive"))
    )
    (net (code "59") (name "VBAT") (class "Default")
      (node (ref "C10") (pin "2") (pinfunction "2_2") (pintype "passive"))
      (node (ref "C9") (pin "1") (pinfunction "1_1") (pintype "passive"))
      (node (ref "D2") (pin "1") (pinfunction "A_1") (pintype "passive"))
      (node (ref "D3") (pin "1") (pinfunction "A_1") (pintype "passive"))
      (node (ref "P2") (pin "2") (pinfunction "2_2") (pintype "passive"))
      (node (ref "R12") (pin "2") (pinfunction "2_2") (pintype "passive"))
      (node (ref "TP5") (pin "1") (pinfunction "T_1") (pintype "passive"))
      (node (ref "U1") (pin "3") (pinfunction "BAT_3") (pintype "passive"))
    )
    (net (code "60") (name "Vin_(5{slash}3.7V)") (class "Default")
      (node (ref "C12") (pin "2") (pinfunction "2_2") (pintype "passive"))
      (node (ref "C6") (pin "2") (pinfunction "2_2") (pintype "passive"))
      (node (ref "C8") (pin "1") (pinfunction "1_1") (pintype "passive"))
      (node (ref "D6") (pin "2") (pinfunction "K_2") (pintype "passive"))
      (node (ref "D7") (pin "2") (pinfunction "K_2") (pintype "passive"))
      (node (ref "F1") (pin "2") (pinfunction "2_2") (pintype "passive"))
      (node (ref "L1") (pin "2") (pinfunction "2_2") (pintype "passive"))
      (node (ref "R3") (pin "1") (pinfunction "1_1") (pintype "passive"))
      (node (ref "U2") (pin "4") (pinfunction "IN_4") (pintype "passive"))
      (node (ref "U3") (pin "1") (pinfunction "Vin_1") (pintype "passive"))
      (node (ref "U3") (pin "3") (pinfunction "CE_3") (pintype "passive"))
    )
    (net (code "61") (name "Vin_5V") (class "Default")
      (node (ref "C11") (pin "2") (pinfunction "2_2") (pintype "passive"))
      (node (ref "C7") (pin "1") (pinfunction "1_1") (pintype "passive"))
      (node (ref "D4") (pin "1") (pinfunction "A_1") (pintype "passive"))
      (node (ref "D5") (pin "1") (pinfunction "A_1") (pintype "passive"))
      (node (ref "P3") (pin "2") (pinfunction "2_2") (pintype "passive"))
      (node (ref "R11") (pin "1") (pinfunction "1_1") (pintype "passive"))
      (node (ref "R17") (pin "1") (pinfunction "1_1") (pintype "passive"))
      (node (ref "TP4") (pin "1") (pinfunction "T_1") (pintype "passive"))
      (node (ref "U1") (pin "4") (pinfunction "VCC_4") (pintype "passive"))
    )
    (net (code "62") (name "Vin_Solar") (class "Default")
      (node (ref "P1") (pin "2") (pinfunction "2_2") (pintype "passive"))
    )
    (net (code "63") (name "Vout_5V") (class "Default")
      (node (ref "C1") (pin "1") (pinfunction "1_1") (pintype "passive"))
      (node (ref "C13") (pin "1") (pinfunction "1_1") (pintype "passive"))
      (node (ref "C2") (pin "1") (pinfunction "1_1") (pintype "passive"))
      (node (ref "C25") (pin "2") (pinfunction "2_2") (pintype "passive"))
      (node (ref "C26") (pin "1") (pinfunction "1_1") (pintype "passive"))
      (node (ref "C3") (pin "2") (pinfunction "2_2") (pintype "passive"))
      (node (ref "P7") (pin "6") (pinfunction "6_6") (pintype "passive"))
      (node (ref "R6") (pin "2") (pinfunction "2_2") (pintype "passive"))
      (node (ref "U2") (pin "10") (pinfunction "OUT_10") (pintype "passive"))
      (node (ref "U2") (pin "9") (pinfunction "OUT_9") (pintype "passive"))
      (node (ref "U6") (pin "13") (pinfunction "DCIN_13") (pintype "passive"))
      (node (ref "U6") (pin "14") (pinfunction "DCIN_14") (pintype "passive"))
    )
    (net (code "64") (name "unconnected-(P6-Pad3)") (class "Default")
      (node (ref "P6") (pin "3") (pinfunction "3_3") (pintype "passive"))
    )
    (net (code "65") (name "unconnected-(P7-Pad2)") (class "Default")
      (node (ref "P7") (pin "2") (pinfunction "2_2") (pintype "passive+no_connect"))
    )
    (net (code "66") (name "unconnected-(P7-Pad9)") (class "Default")
      (node (ref "P7") (pin "9") (pinfunction "9_9") (pintype "passive"))
    )
    (net (code "67") (name "unconnected-(P7-Pad10)") (class "Default")
      (node (ref "P7") (pin "10") (pinfunction "10_10") (pintype "passive"))
    )
    (net (code "68") (name "unconnected-(U3-NC-Pad4)") (class "Default")
      (node (ref "U3") (pin "4") (pinfunction "NC_4") (pintype "passive"))
    )
    (net (code "69") (name "unconnected-(U4-PA0-WKUP{slash}ADC12IN0-Pad10)") (class "Default")
      (node (ref "U4") (pin "10") (pinfunction "PA0-WKUP/ADC12IN0_10") (pintype "passive+no_connect"))
    )
    (net (code "70") (name "unconnected-(U4-PA1{slash}ADC12IN1-Pad11)") (class "Default")
      (node (ref "U4") (pin "11") (pinfunction "PA1/ADC12IN1_11") (pintype "passive+no_connect"))
    )
    (net (code "71") (name "unconnected-(U4-PA8{slash}TMR1_CH1({slash}MCO-Pad29)") (class "Default")
      (node (ref "U4") (pin "29") (pinfunction "PA8/TMR1_CH1(/MCO_29") (pintype "passive+no_connect"))
    )
    (net (code "72") (name "unconnected-(U4-PB2{slash}BOOT1-Pad20)") (class "Default")
      (node (ref "U4") (pin "20") (pinfunction "PB2/BOOT1_20") (pintype "passive+no_connect"))
    )
    (net (code "73") (name "unconnected-(U4-PB9-Pad46)") (class "Default")
      (node (ref "U4") (pin "46") (pinfunction "PB9_46") (pintype "passive+no_connect"))
    )
    (net (code "74") (name "unconnected-(U4-PC13-TAM-RTC-Pad2)") (class "Default")
      (node (ref "U4") (pin "2") (pinfunction "PC13-TAM-RTC_2") (pintype "passive+no_connect"))
    )
    (net (code "75") (name "unconnected-(U4-PC14-OSC32_IN-Pad3)") (class "Default")
      (node (ref "U4") (pin "3") (pinfunction "PC14-OSC32_IN_3") (pintype "passive+no_connect"))
    )
    (net (code "76") (name "unconnected-(U4-PC15-OSC32_OUT-Pad4)") (class "Default")
      (node (ref "U4") (pin "4") (pinfunction "PC15-OSC32_OUT_4") (pintype "passive+no_connect"))
    )
    (net (code "77") (name "unconnected-(U6-NC-Pad17)") (class "Default")
      (node (ref "U6") (pin "17") (pinfunction "NC_17") (pintype "passive+no_connect"))
    )
    (net (code "78") (name "unconnected-(U6-SIM_CLK-Pad22)") (class "Default")
      (node (ref "U6") (pin "22") (pinfunction "SIM_CLK_22") (pintype "passive+no_connect"))
    )
    (net (code "79") (name "unconnected-(U6-SIM_DAT-Pad21)") (class "Default")
      (node (ref "U6") (pin "21") (pinfunction "SIM_DAT_21") (pintype "passive+no_connect"))
    )
    (net (code "80") (name "unconnected-(U6-SIM_RST-Pad23)") (class "Default")
      (node (ref "U6") (pin "23") (pinfunction "SIM_RST_23") (pintype "passive+no_connect"))
    )
    (net (code "81") (name "unconnected-(U6-USB_DM-Pad3)") (class "Default")
      (node (ref "U6") (pin "3") (pinfunction "USB_DM_3") (pintype "passive+no_connect"))
    )
    (net (code "82") (name "unconnected-(U6-USB_DP-Pad4)") (class "Default")
      (node (ref "U6") (pin "4") (pinfunction "USB_DP_4") (pintype "passive+no_connect"))
    )
    (net (code "83") (name "unconnected-(U6-VBUS-Pad8)") (class "Default")
      (node (ref "U6") (pin "8") (pinfunction "VBUS_8") (pintype "passive+no_connect"))
    )
    (net (code "84") (name "unconnected-(U6-VCAP-Pad16)") (class "Default")
      (node (ref "U6") (pin "16") (pinfunction "VCAP_16") (pintype "passive+no_connect"))
    )
    (net (code "85") (name "unconnected-(U6-VSIM-Pad20)") (class "Default")
      (node (ref "U6") (pin "20") (pinfunction "VSIM_20") (pintype "passive+no_connect"))
    )
    (net (code "86") (name "unconnected-(U6-V_PAD-Pad5)") (class "Default")
      (node (ref "U6") (pin "5") (pinfunction "V_PAD_5") (pintype "passive+no_connect"))
    )
  )
)
